# adb.net
KiCad netlist of a schematic drawn in EAGLE
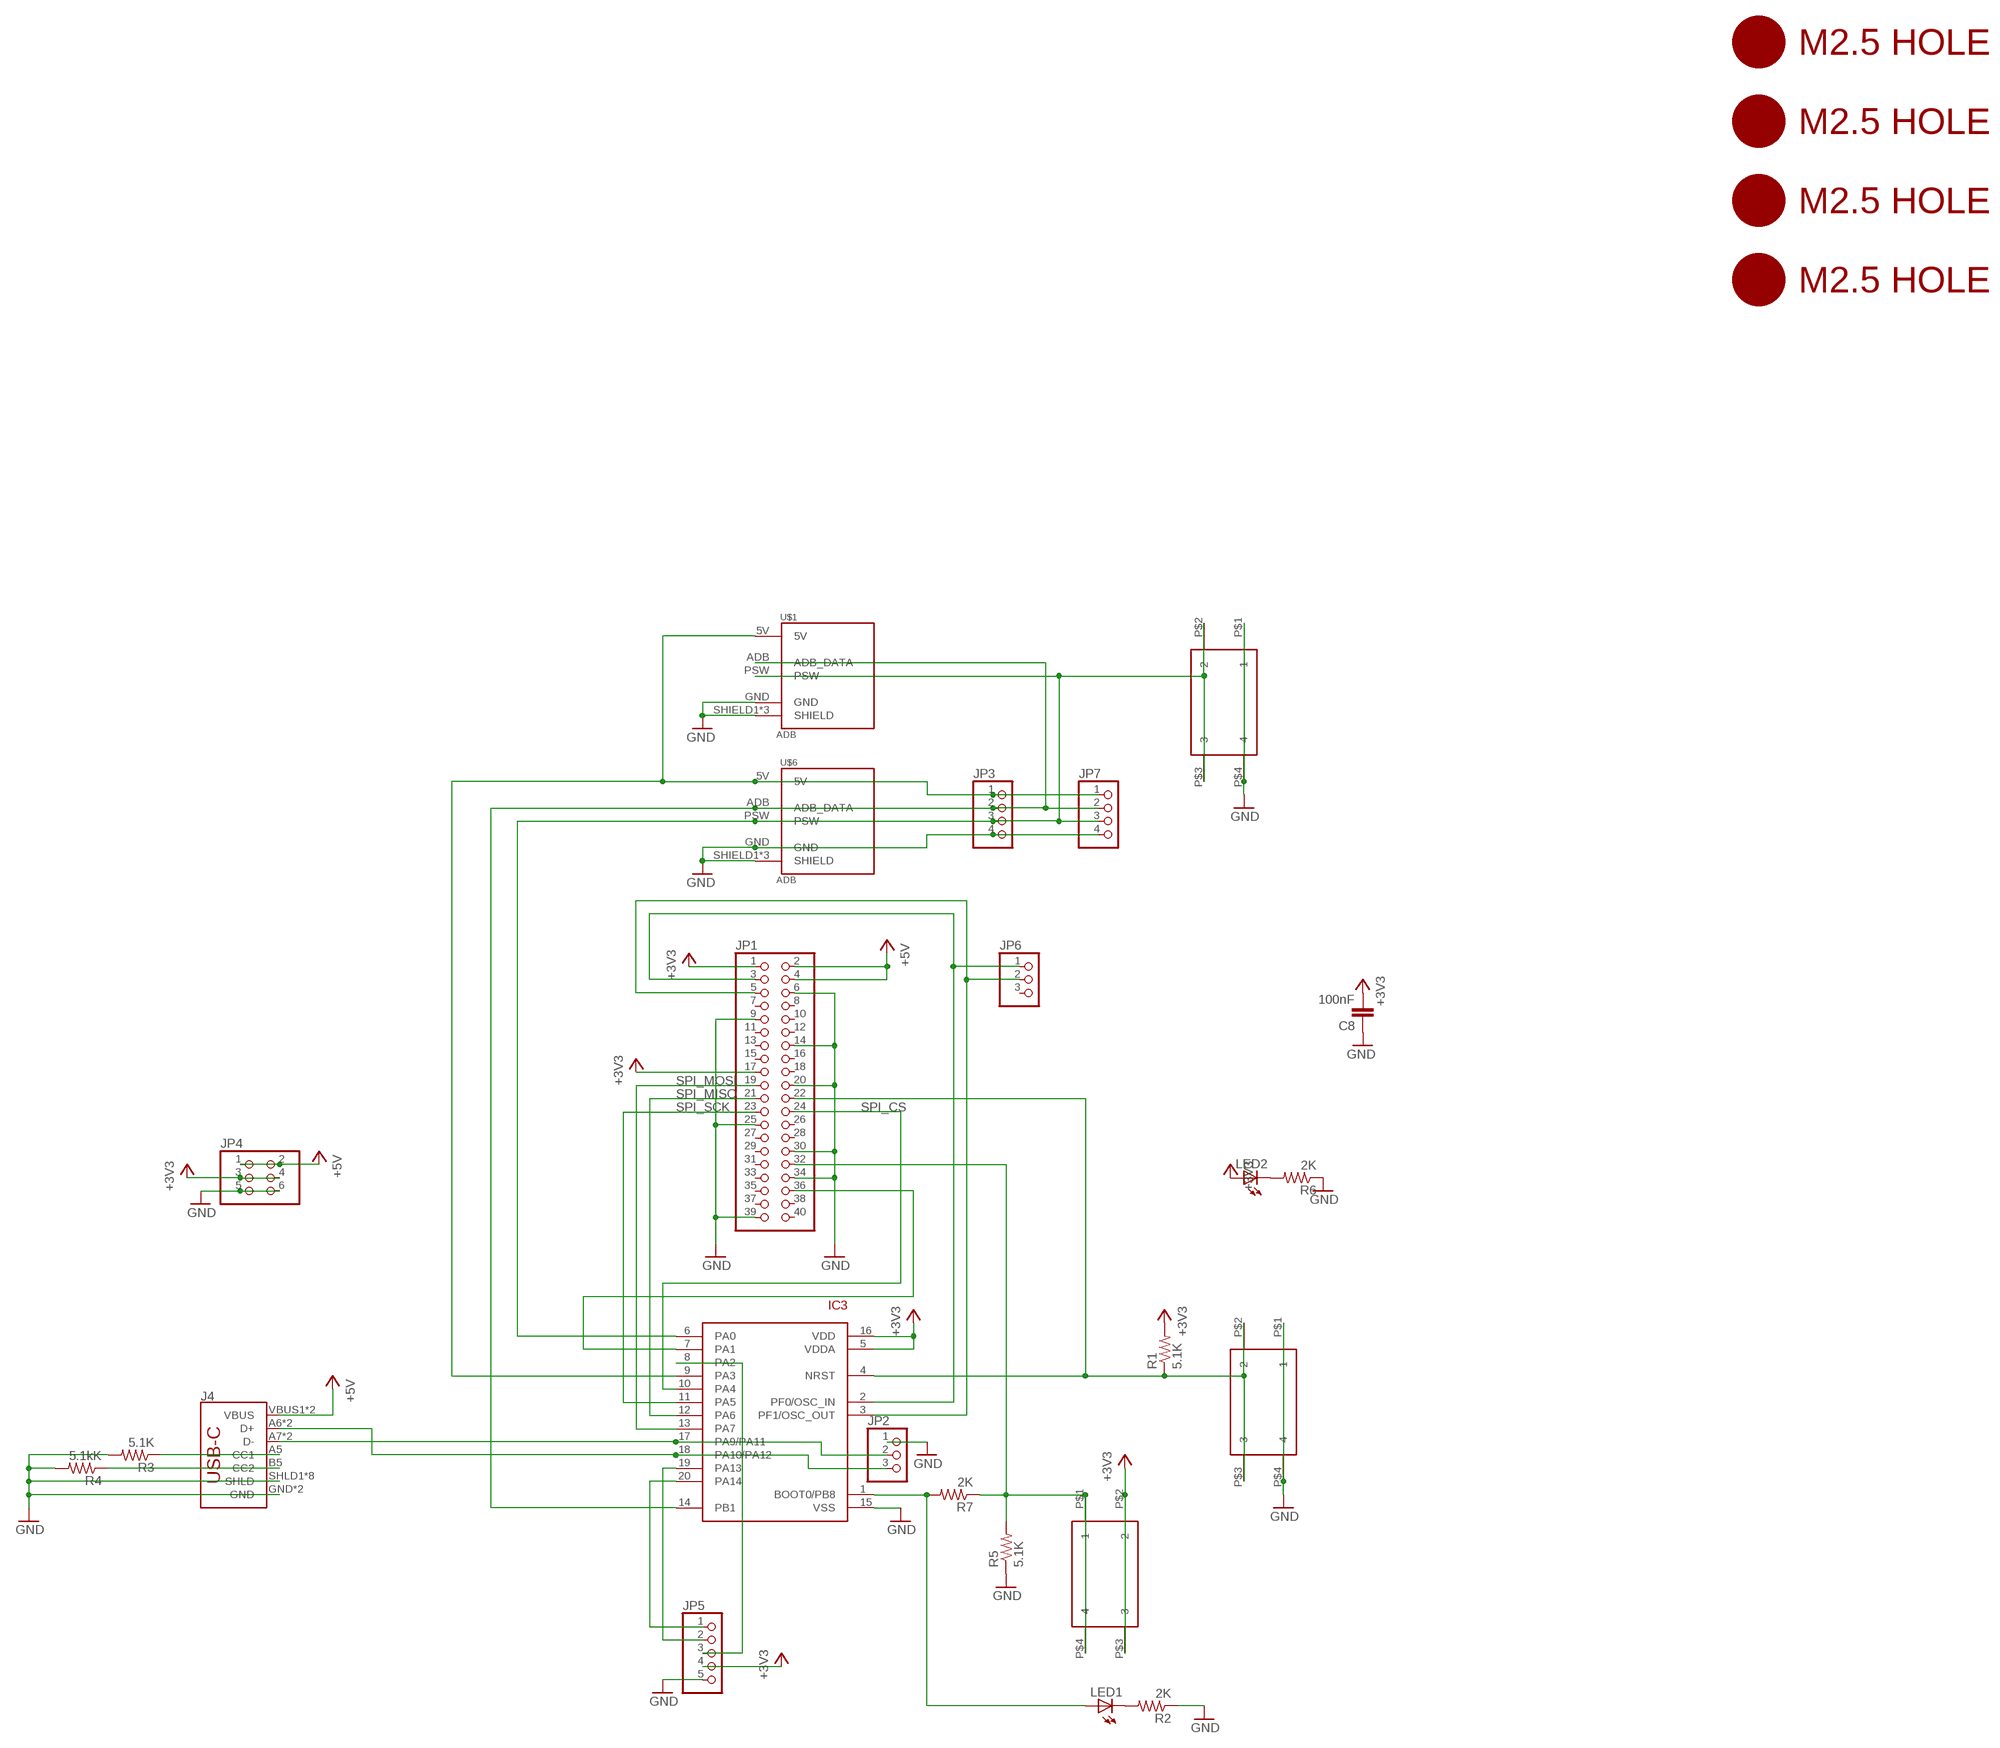
[diagram p0: schematic, sheet 1]

(export (version "E")
  (design (tool "Eeschema 10.0.6"))
  (components
    (comp (ref "C8")
      (value "100nF")
      (footprint "eagle-import:0805@1")
      (libsource (lib "eagle-import") (part "CAP0805"))
    )
    (comp (ref "IC3")
      (value "STM32F042F4")
      (footprint "eagle-import:TSSOP20")
      (libsource (lib "eagle-import") (part "STM32F042F4"))
    )
    (comp (ref "J4")
      (value "USB_C16PIN")
      (footprint "eagle-import:USB-C-16P")
      (libsource (lib "eagle-import") (part "USB_C16PIN"))
    )
    (comp (ref "JP1")
      (value "PINHD-2X20-BIG")
      (footprint "eagle-import:2X20-BIG")
      (libsource (lib "eagle-import") (part "PINHD-2X20-BIG"))
    )
    (comp (ref "JP2")
      (value "PINHD-1X3")
      (footprint "eagle-import:1X03")
      (libsource (lib "eagle-import") (part "PINHD-1X3"))
    )
    (comp (ref "JP3")
      (value "PINHD-1X4")
      (footprint "eagle-import:1X04")
      (libsource (lib "eagle-import") (part "PINHD-1X4"))
    )
    (comp (ref "JP4")
      (value "PINHD-2X3")
      (footprint "eagle-import:2X03")
      (libsource (lib "eagle-import") (part "PINHD-2X3"))
    )
    (comp (ref "JP5")
      (value "PINHD-1X5")
      (footprint "eagle-import:1X05")
      (libsource (lib "eagle-import") (part "PINHD-1X5"))
    )
    (comp (ref "JP6")
      (value "PINHD-1X3")
      (footprint "eagle-import:1X03")
      (libsource (lib "eagle-import") (part "PINHD-1X3"))
    )
    (comp (ref "JP7")
      (value "PINHD-1X4")
      (footprint "eagle-import:1X04")
      (libsource (lib "eagle-import") (part "PINHD-1X4"))
    )
    (comp (ref "LED1")
      (value "LEDCHIP-LED0805")
      (footprint "eagle-import:CHIP-LED0805")
      (libsource (lib "eagle-import") (part "LEDCHIP-LED0805"))
    )
    (comp (ref "LED2")
      (value "LEDCHIP-LED0805")
      (footprint "eagle-import:CHIP-LED0805")
      (libsource (lib "eagle-import") (part "LEDCHIP-LED0805"))
    )
    (comp (ref "R1")
      (value "5.1K")
      (footprint "eagle-import:0805")
      (libsource (lib "eagle-import") (part "RESISTOR0805-RES"))
    )
    (comp (ref "R2")
      (value "2K")
      (footprint "eagle-import:0805")
      (libsource (lib "eagle-import") (part "RESISTOR0805-RES"))
    )
    (comp (ref "R3")
      (value "5.1K")
      (footprint "eagle-import:0805")
      (libsource (lib "eagle-import") (part "RESISTOR0805-RES"))
    )
    (comp (ref "R4")
      (value "5.1kK")
      (footprint "eagle-import:0805")
      (libsource (lib "eagle-import") (part "RESISTOR0805-RES"))
    )
    (comp (ref "R5")
      (value "5.1K")
      (footprint "eagle-import:0805")
      (libsource (lib "eagle-import") (part "RESISTOR0805-RES"))
    )
    (comp (ref "R6")
      (value "2K")
      (footprint "eagle-import:0805")
      (libsource (lib "eagle-import") (part "RESISTOR0805-RES"))
    )
    (comp (ref "R7")
      (value "2K")
      (footprint "eagle-import:0805")
      (libsource (lib "eagle-import") (part "RESISTOR0805-RES"))
    )
    (comp (ref "SW1")
      (value "324_SW")
      (footprint "eagle-import:342_SWICH_FOOT")
      (libsource (lib "eagle-import") (part "324_SW"))
    )
    (comp (ref "SW2")
      (value "324_SW")
      (footprint "eagle-import:342_SWICH_FOOT")
      (libsource (lib "eagle-import") (part "324_SW"))
    )
    (comp (ref "SW4")
      (value "324_SW")
      (footprint "eagle-import:342_SWICH_FOOT")
      (libsource (lib "eagle-import") (part "324_SW"))
    )
    (comp (ref "U$1")
      (value "ADB")
      (footprint "eagle-import:DIN4")
      (libsource (lib "eagle-import") (part "ADB"))
    )
    (comp (ref "U$2")
      (value "M2.5HOLE")
      (footprint "eagle-import:M2.5HOLE")
      (libsource (lib "eagle-import") (part "M2.5HOLE"))
    )
    (comp (ref "U$3")
      (value "M2.5HOLE")
      (footprint "eagle-import:M2.5HOLE")
      (libsource (lib "eagle-import") (part "M2.5HOLE"))
    )
    (comp (ref "U$4")
      (value "M2.5HOLE")
      (footprint "eagle-import:M2.5HOLE")
      (libsource (lib "eagle-import") (part "M2.5HOLE"))
    )
    (comp (ref "U$5")
      (value "M2.5HOLE")
      (footprint "eagle-import:M2.5HOLE")
      (libsource (lib "eagle-import") (part "M2.5HOLE"))
    )
    (comp (ref "U$6")
      (value "ADB")
      (footprint "eagle-import:DIN4")
      (libsource (lib "eagle-import") (part "ADB"))
    )
  )
  (nets
    (net (code "1") (name "+3V3") (class "Default")
      (node (ref "C8") (pin "2") (pinfunction "2_2") (pintype "passive"))
      (node (ref "IC3") (pin "16") (pinfunction "VDD_16") (pintype "bidirectional"))
      (node (ref "IC3") (pin "5") (pinfunction "VDDA_5") (pintype "bidirectional"))
      (node (ref "JP1") (pin "1") (pinfunction "1_1") (pintype "passive"))
      (node (ref "JP1") (pin "17") (pinfunction "17_17") (pintype "passive"))
      (node (ref "JP4") (pin "3") (pinfunction "3_3") (pintype "passive"))
      (node (ref "JP4") (pin "4") (pinfunction "4_4") (pintype "passive"))
      (node (ref "JP5") (pin "4") (pinfunction "4_4") (pintype "passive"))
      (node (ref "LED2") (pin "A") (pinfunction "A_A") (pintype "passive"))
      (node (ref "R1") (pin "2") (pinfunction "2_2") (pintype "passive"))
      (node (ref "SW1") (pin "P$2") (pinfunction "2_P$2") (pintype "bidirectional"))
      (node (ref "SW1") (pin "P$3") (pinfunction "3_P$3") (pintype "bidirectional"))
    )
    (net (code "2") (name "+5V") (class "Default")
      (node (ref "J4") (pin "VBUS1") (pinfunction "VBUS_VBUS1") (pintype "bidirectional"))
      (node (ref "J4") (pin "VBUS2") (pinfunction "VBUS_VBUS2") (pintype "bidirectional"))
      (node (ref "JP1") (pin "2") (pinfunction "2_2") (pintype "passive"))
      (node (ref "JP1") (pin "4") (pinfunction "4_4") (pintype "passive"))
      (node (ref "JP4") (pin "1") (pinfunction "1_1") (pintype "passive"))
      (node (ref "JP4") (pin "2") (pinfunction "2_2") (pintype "passive"))
    )
    (net (code "3") (name "/SPI_CS") (class "Default")
      (node (ref "IC3") (pin "10") (pinfunction "PA4_10") (pintype "bidirectional"))
      (node (ref "JP1") (pin "24") (pinfunction "24_24") (pintype "passive"))
    )
    (net (code "4") (name "/SPI_MISO") (class "Default")
      (node (ref "IC3") (pin "12") (pinfunction "PA6_12") (pintype "bidirectional"))
      (node (ref "JP1") (pin "21") (pinfunction "21_21") (pintype "passive"))
    )
    (net (code "5") (name "/SPI_MOSI") (class "Default")
      (node (ref "IC3") (pin "13") (pinfunction "PA7_13") (pintype "bidirectional"))
      (node (ref "JP1") (pin "19") (pinfunction "19_19") (pintype "passive"))
    )
    (net (code "6") (name "/SPI_SCK") (class "Default")
      (node (ref "IC3") (pin "11") (pinfunction "PA5_11") (pintype "bidirectional"))
      (node (ref "JP1") (pin "23") (pinfunction "23_23") (pintype "passive"))
    )
    (net (code "7") (name "GND") (class "Default")
      (node (ref "C8") (pin "1") (pinfunction "1_1") (pintype "passive"))
      (node (ref "IC3") (pin "15") (pinfunction "VSS_15") (pintype "bidirectional"))
      (node (ref "J4") (pin "GND") (pinfunction "GND_GND") (pintype "bidirectional"))
      (node (ref "J4") (pin "GND2") (pinfunction "GND_GND2") (pintype "bidirectional"))
      (node (ref "J4") (pin "SHLD1") (pinfunction "SHLD_SHLD1") (pintype "bidirectional"))
      (node (ref "J4") (pin "SHLD2") (pinfunction "SHLD_SHLD2") (pintype "bidirectional"))
      (node (ref "J4") (pin "SHLD3") (pinfunction "SHLD_SHLD3") (pintype "bidirectional"))
      (node (ref "J4") (pin "SHLD4") (pinfunction "SHLD_SHLD4") (pintype "bidirectional"))
      (node (ref "J4") (pin "SHLD5") (pinfunction "SHLD_SHLD5") (pintype "bidirectional"))
      (node (ref "J4") (pin "SHLD6") (pinfunction "SHLD_SHLD6") (pintype "bidirectional"))
      (node (ref "J4") (pin "SHLD7") (pinfunction "SHLD_SHLD7") (pintype "bidirectional"))
      (node (ref "J4") (pin "SHLD8") (pinfunction "SHLD_SHLD8") (pintype "bidirectional"))
      (node (ref "JP1") (pin "14") (pinfunction "14_14") (pintype "passive"))
      (node (ref "JP1") (pin "20") (pinfunction "20_20") (pintype "passive"))
      (node (ref "JP1") (pin "25") (pinfunction "25_25") (pintype "passive"))
      (node (ref "JP1") (pin "30") (pinfunction "30_30") (pintype "passive"))
      (node (ref "JP1") (pin "34") (pinfunction "34_34") (pintype "passive"))
      (node (ref "JP1") (pin "39") (pinfunction "39_39") (pintype "passive"))
      (node (ref "JP1") (pin "6") (pinfunction "6_6") (pintype "passive"))
      (node (ref "JP1") (pin "9") (pinfunction "9_9") (pintype "passive"))
      (node (ref "JP2") (pin "1") (pinfunction "1_1") (pintype "passive"))
      (node (ref "JP3") (pin "4") (pinfunction "4_4") (pintype "passive"))
      (node (ref "JP4") (pin "5") (pinfunction "5_5") (pintype "passive"))
      (node (ref "JP4") (pin "6") (pinfunction "6_6") (pintype "passive"))
      (node (ref "JP5") (pin "5") (pinfunction "5_5") (pintype "passive"))
      (node (ref "JP7") (pin "4") (pinfunction "4_4") (pintype "passive"))
      (node (ref "R2") (pin "1") (pinfunction "1_1") (pintype "passive"))
      (node (ref "R3") (pin "2") (pinfunction "2_2") (pintype "passive"))
      (node (ref "R4") (pin "2") (pinfunction "2_2") (pintype "passive"))
      (node (ref "R5") (pin "1") (pinfunction "1_1") (pintype "passive"))
      (node (ref "R6") (pin "1") (pinfunction "1_1") (pintype "passive"))
      (node (ref "SW2") (pin "P$1") (pinfunction "1_P$1") (pintype "bidirectional"))
      (node (ref "SW2") (pin "P$4") (pinfunction "4_P$4") (pintype "bidirectional"))
      (node (ref "SW4") (pin "P$1") (pinfunction "1_P$1") (pintype "bidirectional"))
      (node (ref "SW4") (pin "P$4") (pinfunction "4_P$4") (pintype "bidirectional"))
      (node (ref "U$1") (pin "GND") (pinfunction "GND_GND") (pintype "bidirectional"))
      (node (ref "U$1") (pin "SHIELD1") (pinfunction "SHIELD_SHIELD1") (pintype "bidirectional"))
      (node (ref "U$1") (pin "SHIELD2") (pinfunction "SHIELD_SHIELD2") (pintype "bidirectional"))
      (node (ref "U$1") (pin "SHIELD3") (pinfunction "SHIELD_SHIELD3") (pintype "bidirectional"))
      (node (ref "U$6") (pin "GND") (pinfunction "GND_GND") (pintype "bidirectional"))
      (node (ref "U$6") (pin "SHIELD1") (pinfunction "SHIELD_SHIELD1") (pintype "bidirectional"))
      (node (ref "U$6") (pin "SHIELD2") (pinfunction "SHIELD_SHIELD2") (pintype "bidirectional"))
      (node (ref "U$6") (pin "SHIELD3") (pinfunction "SHIELD_SHIELD3") (pintype "bidirectional"))
    )
    (net (code "8") (name "Net-(IC3-BOOT0{slash}PB8)") (class "Default")
      (node (ref "IC3") (pin "1") (pinfunction "BOOT0/PB8_1") (pintype "bidirectional"))
      (node (ref "LED1") (pin "A") (pinfunction "A_A") (pintype "passive"))
      (node (ref "R7") (pin "2") (pinfunction "2_2") (pintype "passive"))
    )
    (net (code "9") (name "Net-(IC3-NRST)") (class "Default")
      (node (ref "IC3") (pin "4") (pinfunction "NRST_4") (pintype "bidirectional"))
      (node (ref "JP1") (pin "22") (pinfunction "22_22") (pintype "passive"))
      (node (ref "R1") (pin "1") (pinfunction "1_1") (pintype "passive"))
      (node (ref "SW4") (pin "P$2") (pinfunction "2_P$2") (pintype "bidirectional"))
      (node (ref "SW4") (pin "P$3") (pinfunction "3_P$3") (pintype "bidirectional"))
    )
    (net (code "10") (name "Net-(IC3-PA0)") (class "Default")
      (node (ref "IC3") (pin "6") (pinfunction "PA0_6") (pintype "bidirectional"))
      (node (ref "JP3") (pin "3") (pinfunction "3_3") (pintype "passive"))
      (node (ref "JP7") (pin "3") (pinfunction "3_3") (pintype "passive"))
      (node (ref "SW2") (pin "P$2") (pinfunction "2_P$2") (pintype "bidirectional"))
      (node (ref "SW2") (pin "P$3") (pinfunction "3_P$3") (pintype "bidirectional"))
      (node (ref "U$1") (pin "PSW") (pinfunction "PSW_PSW") (pintype "bidirectional"))
      (node (ref "U$6") (pin "PSW") (pinfunction "PSW_PSW") (pintype "bidirectional"))
    )
    (net (code "11") (name "Net-(IC3-PA1)") (class "Default")
      (node (ref "IC3") (pin "7") (pinfunction "PA1_7") (pintype "bidirectional"))
      (node (ref "JP1") (pin "36") (pinfunction "36_36") (pintype "passive"))
    )
    (net (code "12") (name "Net-(IC3-PA2)") (class "Default")
      (node (ref "IC3") (pin "8") (pinfunction "PA2_8") (pintype "bidirectional"))
      (node (ref "JP5") (pin "3") (pinfunction "3_3") (pintype "passive"))
    )
    (net (code "13") (name "Net-(IC3-PA3)") (class "Default")
      (node (ref "IC3") (pin "9") (pinfunction "PA3_9") (pintype "bidirectional"))
      (node (ref "JP3") (pin "1") (pinfunction "1_1") (pintype "passive"))
      (node (ref "JP7") (pin "1") (pinfunction "1_1") (pintype "passive"))
      (node (ref "U$1") (pin "5V") (pinfunction "5V_5V") (pintype "bidirectional"))
      (node (ref "U$6") (pin "5V") (pinfunction "5V_5V") (pintype "bidirectional"))
    )
    (net (code "14") (name "Net-(IC3-PA9{slash}PA11)") (class "Default")
      (node (ref "IC3") (pin "17") (pinfunction "PA9/PA11_17") (pintype "bidirectional"))
      (node (ref "J4") (pin "A7") (pinfunction "D-_A7") (pintype "bidirectional"))
      (node (ref "J4") (pin "B7") (pinfunction "D-_B7") (pintype "bidirectional"))
      (node (ref "JP2") (pin "2") (pinfunction "2_2") (pintype "passive"))
    )
    (net (code "15") (name "Net-(IC3-PA10{slash}PA12)") (class "Default")
      (node (ref "IC3") (pin "18") (pinfunction "PA10/PA12_18") (pintype "bidirectional"))
      (node (ref "J4") (pin "A6") (pinfunction "D+_A6") (pintype "bidirectional"))
      (node (ref "J4") (pin "B6") (pinfunction "D+_B6") (pintype "bidirectional"))
      (node (ref "JP2") (pin "3") (pinfunction "3_3") (pintype "passive"))
    )
    (net (code "16") (name "Net-(IC3-PA13)") (class "Default")
      (node (ref "IC3") (pin "19") (pinfunction "PA13_19") (pintype "bidirectional"))
      (node (ref "JP5") (pin "2") (pinfunction "2_2") (pintype "passive"))
    )
    (net (code "17") (name "Net-(IC3-PA14)") (class "Default")
      (node (ref "IC3") (pin "20") (pinfunction "PA14_20") (pintype "bidirectional"))
      (node (ref "JP5") (pin "1") (pinfunction "1_1") (pintype "passive"))
    )
    (net (code "18") (name "Net-(IC3-PB1)") (class "Default")
      (node (ref "IC3") (pin "14") (pinfunction "PB1_14") (pintype "bidirectional"))
      (node (ref "JP3") (pin "2") (pinfunction "2_2") (pintype "passive"))
      (node (ref "JP7") (pin "2") (pinfunction "2_2") (pintype "passive"))
      (node (ref "U$1") (pin "ADB") (pinfunction "ADB_DATA_ADB") (pintype "bidirectional"))
      (node (ref "U$6") (pin "ADB") (pinfunction "ADB_DATA_ADB") (pintype "bidirectional"))
    )
    (net (code "19") (name "Net-(IC3-PF0{slash}OSC_IN)") (class "Default")
      (node (ref "IC3") (pin "2") (pinfunction "PF0/OSC_IN_2") (pintype "bidirectional"))
      (node (ref "JP1") (pin "3") (pinfunction "3_3") (pintype "passive"))
      (node (ref "JP6") (pin "1") (pinfunction "1_1") (pintype "passive"))
    )
    (net (code "20") (name "Net-(IC3-PF1{slash}OSC_OUT)") (class "Default")
      (node (ref "IC3") (pin "3") (pinfunction "PF1/OSC_OUT_3") (pintype "bidirectional"))
      (node (ref "JP1") (pin "5") (pinfunction "5_5") (pintype "passive"))
      (node (ref "JP6") (pin "2") (pinfunction "2_2") (pintype "passive"))
    )
    (net (code "21") (name "Net-(J4-CC1)") (class "Default")
      (node (ref "J4") (pin "A5") (pinfunction "CC1_A5") (pintype "bidirectional"))
      (node (ref "R3") (pin "1") (pinfunction "1_1") (pintype "passive"))
    )
    (net (code "22") (name "Net-(J4-CC2)") (class "Default")
      (node (ref "J4") (pin "B5") (pinfunction "CC2_B5") (pintype "bidirectional"))
      (node (ref "R4") (pin "1") (pinfunction "1_1") (pintype "passive"))
    )
    (net (code "23") (name "Net-(LED1-PadC)") (class "Default")
      (node (ref "LED1") (pin "C") (pinfunction "C_C") (pintype "passive"))
      (node (ref "R2") (pin "2") (pinfunction "2_2") (pintype "passive"))
    )
    (net (code "24") (name "Net-(LED2-PadC)") (class "Default")
      (node (ref "LED2") (pin "C") (pinfunction "C_C") (pintype "passive"))
      (node (ref "R6") (pin "2") (pinfunction "2_2") (pintype "passive"))
    )
    (net (code "25") (name "Net-(SW1-1)") (class "Default")
      (node (ref "JP1") (pin "32") (pinfunction "32_32") (pintype "passive"))
      (node (ref "R5") (pin "2") (pinfunction "2_2") (pintype "passive"))
      (node (ref "R7") (pin "1") (pinfunction "1_1") (pintype "passive"))
      (node (ref "SW1") (pin "P$1") (pinfunction "1_P$1") (pintype "bidirectional"))
      (node (ref "SW1") (pin "P$4") (pinfunction "4_P$4") (pintype "bidirectional"))
    )
    (net (code "26") (name "unconnected-(JP1-Pad7)") (class "Default")
      (node (ref "JP1") (pin "7") (pinfunction "7_7") (pintype "passive"))
    )
    (net (code "27") (name "unconnected-(JP1-Pad8)") (class "Default")
      (node (ref "JP1") (pin "8") (pinfunction "8_8") (pintype "passive"))
    )
    (net (code "28") (name "unconnected-(JP1-Pad10)") (class "Default")
      (node (ref "JP1") (pin "10") (pinfunction "10_10") (pintype "passive"))
    )
    (net (code "29") (name "unconnected-(JP1-Pad11)") (class "Default")
      (node (ref "JP1") (pin "11") (pinfunction "11_11") (pintype "passive"))
    )
    (net (code "30") (name "unconnected-(JP1-Pad12)") (class "Default")
      (node (ref "JP1") (pin "12") (pinfunction "12_12") (pintype "passive"))
    )
    (net (code "31") (name "unconnected-(JP1-Pad13)") (class "Default")
      (node (ref "JP1") (pin "13") (pinfunction "13_13") (pintype "passive"))
    )
    (net (code "32") (name "unconnected-(JP1-Pad15)") (class "Default")
      (node (ref "JP1") (pin "15") (pinfunction "15_15") (pintype "passive"))
    )
    (net (code "33") (name "unconnected-(JP1-Pad16)") (class "Default")
      (node (ref "JP1") (pin "16") (pinfunction "16_16") (pintype "passive"))
    )
    (net (code "34") (name "unconnected-(JP1-Pad18)") (class "Default")
      (node (ref "JP1") (pin "18") (pinfunction "18_18") (pintype "passive"))
    )
    (net (code "35") (name "unconnected-(JP1-Pad26)") (class "Default")
      (node (ref "JP1") (pin "26") (pinfunction "26_26") (pintype "passive"))
    )
    (net (code "36") (name "unconnected-(JP1-Pad27)") (class "Default")
      (node (ref "JP1") (pin "27") (pinfunction "27_27") (pintype "passive"))
    )
    (net (code "37") (name "unconnected-(JP1-Pad28)") (class "Default")
      (node (ref "JP1") (pin "28") (pinfunction "28_28") (pintype "passive"))
    )
    (net (code "38") (name "unconnected-(JP1-Pad29)") (class "Default")
      (node (ref "JP1") (pin "29") (pinfunction "29_29") (pintype "passive"))
    )
    (net (code "39") (name "unconnected-(JP1-Pad31)") (class "Default")
      (node (ref "JP1") (pin "31") (pinfunction "31_31") (pintype "passive"))
    )
    (net (code "40") (name "unconnected-(JP1-Pad33)") (class "Default")
      (node (ref "JP1") (pin "33") (pinfunction "33_33") (pintype "passive"))
    )
    (net (code "41") (name "unconnected-(JP1-Pad35)") (class "Default")
      (node (ref "JP1") (pin "35") (pinfunction "35_35") (pintype "passive"))
    )
    (net (code "42") (name "unconnected-(JP1-Pad37)") (class "Default")
      (node (ref "JP1") (pin "37") (pinfunction "37_37") (pintype "passive"))
    )
    (net (code "43") (name "unconnected-(JP1-Pad38)") (class "Default")
      (node (ref "JP1") (pin "38") (pinfunction "38_38") (pintype "passive"))
    )
    (net (code "44") (name "unconnected-(JP1-Pad40)") (class "Default")
      (node (ref "JP1") (pin "40") (pinfunction "40_40") (pintype "passive"))
    )
    (net (code "45") (name "unconnected-(JP6-Pad3)") (class "Default")
      (node (ref "JP6") (pin "3") (pinfunction "3_3") (pintype "passive"))
    )
  )
)
